# 5_way_switch_schematic.net
KiCad netlist of a schematic drawn in EAGLE
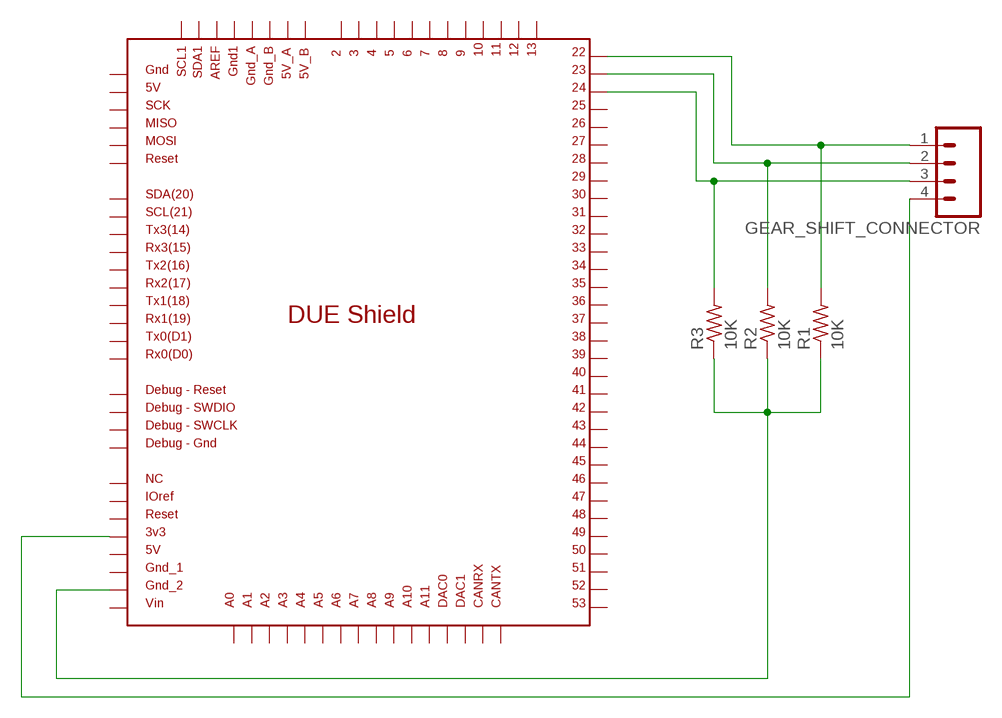
[diagram p0: schematic, sheet 1]

(export (version "E")
  (design (tool "Eeschema 10.0.6"))
  (components
    (comp (ref "GEAR_SHIFT_CONNECTOR")
      (value "M04JST-PTH-VERT")
      (footprint "eagle-import:JST-4-PTH-VERT")
      (libsource (lib "eagle-import") (part "M04JST-PTH-VERT"))
    )
    (comp (ref "R1")
      (value "10K")
      (footprint "eagle-import:0204_5")
      (libsource (lib "eagle-import") (part "R-US_0204/5"))
    )
    (comp (ref "R2")
      (value "10K")
      (footprint "eagle-import:0204_5")
      (libsource (lib "eagle-import") (part "R-US_0204/5"))
    )
    (comp (ref "R3")
      (value "10K")
      (footprint "eagle-import:0204_5")
      (libsource (lib "eagle-import") (part "R-US_0204/5"))
    )
    (comp (ref "U$1")
      (value "DUE(NORMAL)")
      (footprint "eagle-import:DUE(NORMAL)")
      (libsource (lib "eagle-import") (part "DUE(NORMAL)"))
    )
  )
  (nets
    (net (code "1") (name "Net-(GEAR_SHIFT_CONNECTOR-Pad1)") (class "Default")
      (node (ref "GEAR_SHIFT_CONNECTOR") (pin "1") (pinfunction "1_1") (pintype "passive"))
      (node (ref "R1") (pin "2") (pinfunction "2_2") (pintype "passive"))
      (node (ref "U$1") (pin "22") (pinfunction "22_22") (pintype "bidirectional"))
    )
    (net (code "2") (name "Net-(GEAR_SHIFT_CONNECTOR-Pad2)") (class "Default")
      (node (ref "GEAR_SHIFT_CONNECTOR") (pin "2") (pinfunction "2_2") (pintype "passive"))
      (node (ref "R2") (pin "2") (pinfunction "2_2") (pintype "passive"))
      (node (ref "U$1") (pin "23") (pinfunction "23_23") (pintype "bidirectional"))
    )
    (net (code "3") (name "Net-(GEAR_SHIFT_CONNECTOR-Pad3)") (class "Default")
      (node (ref "GEAR_SHIFT_CONNECTOR") (pin "3") (pinfunction "3_3") (pintype "passive"))
      (node (ref "R3") (pin "2") (pinfunction "2_2") (pintype "passive"))
      (node (ref "U$1") (pin "24") (pinfunction "24_24") (pintype "bidirectional"))
    )
    (net (code "4") (name "Net-(GEAR_SHIFT_CONNECTOR-Pad4)") (class "Default")
      (node (ref "GEAR_SHIFT_CONNECTOR") (pin "4") (pinfunction "4_4") (pintype "passive"))
      (node (ref "U$1") (pin "3V3") (pinfunction "3V3_3V3") (pintype "bidirectional"))
    )
    (net (code "5") (name "Net-(R1-Pad1)") (class "Default")
      (node (ref "R1") (pin "1") (pinfunction "1_1") (pintype "passive"))
      (node (ref "R2") (pin "1") (pinfunction "1_1") (pintype "passive"))
      (node (ref "R3") (pin "1") (pinfunction "1_1") (pintype "passive"))
      (node (ref "U$1") (pin "GND_2") (pinfunction "GND_2_GND_2") (pintype "bidirectional"))
    )
    (net (code "6") (name "unconnected-(U$1-Pad2)") (class "Default")
      (node (ref "U$1") (pin "2") (pinfunction "2_2") (pintype "bidirectional"))
    )
    (net (code "7") (name "unconnected-(U$1-Pad3)") (class "Default")
      (node (ref "U$1") (pin "3") (pinfunction "3_3") (pintype "bidirectional"))
    )
    (net (code "8") (name "unconnected-(U$1-Pad4)") (class "Default")
      (node (ref "U$1") (pin "4") (pinfunction "4_4") (pintype "bidirectional"))
    )
    (net (code "9") (name "unconnected-(U$1-Pad5)") (class "Default")
      (node (ref "U$1") (pin "5") (pinfunction "5_5") (pintype "bidirectional"))
    )
    (net (code "10") (name "unconnected-(U$1-Pad5V)") (class "Default")
      (node (ref "U$1") (pin "5V") (pinfunction "5V_5V") (pintype "bidirectional"))
    )
    (net (code "11") (name "unconnected-(U$1-Pad5V_A)") (class "Default")
      (node (ref "U$1") (pin "5V_A") (pinfunction "5V_A_5V_A") (pintype "bidirectional"))
    )
    (net (code "12") (name "unconnected-(U$1-Pad5V_B)") (class "Default")
      (node (ref "U$1") (pin "5V_B") (pinfunction "5V_B_5V_B") (pintype "bidirectional"))
    )
    (net (code "13") (name "unconnected-(U$1-Pad5V_ICSP)") (class "Default")
      (node (ref "U$1") (pin "5V_ICSP") (pinfunction "5V_ICSP_5V_ICSP") (pintype "bidirectional"))
    )
    (net (code "14") (name "unconnected-(U$1-Pad6)") (class "Default")
      (node (ref "U$1") (pin "6") (pinfunction "6_6") (pintype "bidirectional"))
    )
    (net (code "15") (name "unconnected-(U$1-Pad7)") (class "Default")
      (node (ref "U$1") (pin "7") (pinfunction "7_7") (pintype "bidirectional"))
    )
    (net (code "16") (name "unconnected-(U$1-Pad8)") (class "Default")
      (node (ref "U$1") (pin "8") (pinfunction "8_8") (pintype "bidirectional"))
    )
    (net (code "17") (name "unconnected-(U$1-Pad9)") (class "Default")
      (node (ref "U$1") (pin "9") (pinfunction "9_9") (pintype "bidirectional"))
    )
    (net (code "18") (name "unconnected-(U$1-Pad10)") (class "Default")
      (node (ref "U$1") (pin "10") (pinfunction "10_10") (pintype "bidirectional"))
    )
    (net (code "19") (name "unconnected-(U$1-Pad11)") (class "Default")
      (node (ref "U$1") (pin "11") (pinfunction "11_11") (pintype "bidirectional"))
    )
    (net (code "20") (name "unconnected-(U$1-Pad12)") (class "Default")
      (node (ref "U$1") (pin "12") (pinfunction "12_12") (pintype "bidirectional"))
    )
    (net (code "21") (name "unconnected-(U$1-Pad13)") (class "Default")
      (node (ref "U$1") (pin "13") (pinfunction "13_13") (pintype "bidirectional"))
    )
    (net (code "22") (name "unconnected-(U$1-Pad25)") (class "Default")
      (node (ref "U$1") (pin "25") (pinfunction "25_25") (pintype "bidirectional"))
    )
    (net (code "23") (name "unconnected-(U$1-Pad26)") (class "Default")
      (node (ref "U$1") (pin "26") (pinfunction "26_26") (pintype "bidirectional"))
    )
    (net (code "24") (name "unconnected-(U$1-Pad27)") (class "Default")
      (node (ref "U$1") (pin "27") (pinfunction "27_27") (pintype "bidirectional"))
    )
    (net (code "25") (name "unconnected-(U$1-Pad28)") (class "Default")
      (node (ref "U$1") (pin "28") (pinfunction "28_28") (pintype "bidirectional"))
    )
    (net (code "26") (name "unconnected-(U$1-Pad29)") (class "Default")
      (node (ref "U$1") (pin "29") (pinfunction "29_29") (pintype "bidirectional"))
    )
    (net (code "27") (name "unconnected-(U$1-Pad30)") (class "Default")
      (node (ref "U$1") (pin "30") (pinfunction "30_30") (pintype "bidirectional"))
    )
    (net (code "28") (name "unconnected-(U$1-Pad31)") (class "Default")
      (node (ref "U$1") (pin "31") (pinfunction "31_31") (pintype "bidirectional"))
    )
    (net (code "29") (name "unconnected-(U$1-Pad32)") (class "Default")
      (node (ref "U$1") (pin "32") (pinfunction "32_32") (pintype "bidirectional"))
    )
    (net (code "30") (name "unconnected-(U$1-Pad33)") (class "Default")
      (node (ref "U$1") (pin "33") (pinfunction "33_33") (pintype "bidirectional"))
    )
    (net (code "31") (name "unconnected-(U$1-Pad34)") (class "Default")
      (node (ref "U$1") (pin "34") (pinfunction "34_34") (pintype "bidirectional"))
    )
    (net (code "32") (name "unconnected-(U$1-Pad35)") (class "Default")
      (node (ref "U$1") (pin "35") (pinfunction "35_35") (pintype "bidirectional"))
    )
    (net (code "33") (name "unconnected-(U$1-Pad36)") (class "Default")
      (node (ref "U$1") (pin "36") (pinfunction "36_36") (pintype "bidirectional"))
    )
    (net (code "34") (name "unconnected-(U$1-Pad37)") (class "Default")
      (node (ref "U$1") (pin "37") (pinfunction "37_37") (pintype "bidirectional"))
    )
    (net (code "35") (name "unconnected-(U$1-Pad38)") (class "Default")
      (node (ref "U$1") (pin "38") (pinfunction "38_38") (pintype "bidirectional"))
    )
    (net (code "36") (name "unconnected-(U$1-Pad39)") (class "Default")
      (node (ref "U$1") (pin "39") (pinfunction "39_39") (pintype "bidirectional"))
    )
    (net (code "37") (name "unconnected-(U$1-Pad40)") (class "Default")
      (node (ref "U$1") (pin "40") (pinfunction "40_40") (pintype "bidirectional"))
    )
    (net (code "38") (name "unconnected-(U$1-Pad41)") (class "Default")
      (node (ref "U$1") (pin "41") (pinfunction "41_41") (pintype "bidirectional"))
    )
    (net (code "39") (name "unconnected-(U$1-Pad42)") (class "Default")
      (node (ref "U$1") (pin "42") (pinfunction "42_42") (pintype "bidirectional"))
    )
    (net (code "40") (name "unconnected-(U$1-Pad43)") (class "Default")
      (node (ref "U$1") (pin "43") (pinfunction "43_43") (pintype "bidirectional"))
    )
    (net (code "41") (name "unconnected-(U$1-Pad44)") (class "Default")
      (node (ref "U$1") (pin "44") (pinfunction "44_44") (pintype "bidirectional"))
    )
    (net (code "42") (name "unconnected-(U$1-Pad45)") (class "Default")
      (node (ref "U$1") (pin "45") (pinfunction "45_45") (pintype "bidirectional"))
    )
    (net (code "43") (name "unconnected-(U$1-Pad46)") (class "Default")
      (node (ref "U$1") (pin "46") (pinfunction "46_46") (pintype "bidirectional"))
    )
    (net (code "44") (name "unconnected-(U$1-Pad47)") (class "Default")
      (node (ref "U$1") (pin "47") (pinfunction "47_47") (pintype "bidirectional"))
    )
    (net (code "45") (name "unconnected-(U$1-Pad48)") (class "Default")
      (node (ref "U$1") (pin "48") (pinfunction "48_48") (pintype "bidirectional"))
    )
    (net (code "46") (name "unconnected-(U$1-Pad49)") (class "Default")
      (node (ref "U$1") (pin "49") (pinfunction "49_49") (pintype "bidirectional"))
    )
    (net (code "47") (name "unconnected-(U$1-Pad50)") (class "Default")
      (node (ref "U$1") (pin "50") (pinfunction "50_50") (pintype "bidirectional"))
    )
    (net (code "48") (name "unconnected-(U$1-Pad51)") (class "Default")
      (node (ref "U$1") (pin "51") (pinfunction "51_51") (pintype "bidirectional"))
    )
    (net (code "49") (name "unconnected-(U$1-Pad52)") (class "Default")
      (node (ref "U$1") (pin "52") (pinfunction "52_52") (pintype "bidirectional"))
    )
    (net (code "50") (name "unconnected-(U$1-Pad53)") (class "Default")
      (node (ref "U$1") (pin "53") (pinfunction "53_53") (pintype "bidirectional"))
    )
    (net (code "51") (name "unconnected-(U$1-PadA0)") (class "Default")
      (node (ref "U$1") (pin "A0") (pinfunction "A0_A0") (pintype "bidirectional"))
    )
    (net (code "52") (name "unconnected-(U$1-PadA1)") (class "Default")
      (node (ref "U$1") (pin "A1") (pinfunction "A1_A1") (pintype "bidirectional"))
    )
    (net (code "53") (name "unconnected-(U$1-PadA2)") (class "Default")
      (node (ref "U$1") (pin "A2") (pinfunction "A2_A2") (pintype "bidirectional"))
    )
    (net (code "54") (name "unconnected-(U$1-PadA3)") (class "Default")
      (node (ref "U$1") (pin "A3") (pinfunction "A3_A3") (pintype "bidirectional"))
    )
    (net (code "55") (name "unconnected-(U$1-PadA4)") (class "Default")
      (node (ref "U$1") (pin "A4") (pinfunction "A4_A4") (pintype "bidirectional"))
    )
    (net (code "56") (name "unconnected-(U$1-PadA5)") (class "Default")
      (node (ref "U$1") (pin "A5") (pinfunction "A5_A5") (pintype "bidirectional"))
    )
    (net (code "57") (name "unconnected-(U$1-PadA6)") (class "Default")
      (node (ref "U$1") (pin "A6") (pinfunction "A6_A6") (pintype "bidirectional"))
    )
    (net (code "58") (name "unconnected-(U$1-PadA7)") (class "Default")
      (node (ref "U$1") (pin "A7") (pinfunction "A7_A7") (pintype "bidirectional"))
    )
    (net (code "59") (name "unconnected-(U$1-PadA8)") (class "Default")
      (node (ref "U$1") (pin "A8") (pinfunction "A8_A8") (pintype "bidirectional"))
    )
    (net (code "60") (name "unconnected-(U$1-PadA9)") (class "Default")
      (node (ref "U$1") (pin "A9") (pinfunction "A9_A9") (pintype "bidirectional"))
    )
    (net (code "61") (name "unconnected-(U$1-PadA10)") (class "Default")
      (node (ref "U$1") (pin "A10") (pinfunction "A10_A10") (pintype "bidirectional"))
    )
    (net (code "62") (name "unconnected-(U$1-PadA11)") (class "Default")
      (node (ref "U$1") (pin "A11") (pinfunction "A11_A11") (pintype "bidirectional"))
    )
    (net (code "63") (name "unconnected-(U$1-PadAREF)") (class "Default")
      (node (ref "U$1") (pin "AREF") (pinfunction "AREF_AREF") (pintype "bidirectional"))
    )
    (net (code "64") (name "unconnected-(U$1-PadCANRX)") (class "Default")
      (node (ref "U$1") (pin "CANRX") (pinfunction "CANRX_CANRX") (pintype "bidirectional"))
    )
    (net (code "65") (name "unconnected-(U$1-PadCANTX)") (class "Default")
      (node (ref "U$1") (pin "CANTX") (pinfunction "CANTX_CANTX") (pintype "bidirectional"))
    )
    (net (code "66") (name "unconnected-(U$1-PadDAC0)") (class "Default")
      (node (ref "U$1") (pin "DAC0") (pinfunction "DAC0_DAC0") (pintype "bidirectional"))
    )
    (net (code "67") (name "unconnected-(U$1-PadDAC1)") (class "Default")
      (node (ref "U$1") (pin "DAC1") (pinfunction "DAC1_DAC1") (pintype "bidirectional"))
    )
    (net (code "68") (name "unconnected-(U$1-PadGND1)") (class "Default")
      (node (ref "U$1") (pin "GND1") (pinfunction "GND1_GND1") (pintype "bidirectional"))
    )
    (net (code "69") (name "unconnected-(U$1-PadGND_1)") (class "Default")
      (node (ref "U$1") (pin "GND_1") (pinfunction "GND_1_GND_1") (pintype "bidirectional"))
    )
    (net (code "70") (name "unconnected-(U$1-PadGND_A)") (class "Default")
      (node (ref "U$1") (pin "GND_A") (pinfunction "GND_A_GND_A") (pintype "bidirectional"))
    )
    (net (code "71") (name "unconnected-(U$1-PadGND_B)") (class "Default")
      (node (ref "U$1") (pin "GND_B") (pinfunction "GND_B_GND_B") (pintype "bidirectional"))
    )
    (net (code "72") (name "unconnected-(U$1-PadGND_DEBUG)") (class "Default")
      (node (ref "U$1") (pin "GND_DEBUG") (pinfunction "GND_DEBUG_GND_DEBUG") (pintype "bidirectional"))
    )
    (net (code "73") (name "unconnected-(U$1-PadGND_ICSP)") (class "Default")
      (node (ref "U$1") (pin "GND_ICSP") (pinfunction "GND_ICSP_GND_ICSP") (pintype "bidirectional"))
    )
    (net (code "74") (name "unconnected-(U$1-PadIOREF)") (class "Default")
      (node (ref "U$1") (pin "IOREF") (pinfunction "IOREF_IOREF") (pintype "bidirectional"))
    )
    (net (code "75") (name "unconnected-(U$1-PadMISO_ICSP)") (class "Default")
      (node (ref "U$1") (pin "MISO_ICSP") (pinfunction "MISO_ICSP_MISO_ICSP") (pintype "bidirectional"))
    )
    (net (code "76") (name "unconnected-(U$1-PadMOSI_ICSP)") (class "Default")
      (node (ref "U$1") (pin "MOSI_ICSP") (pinfunction "MOSI_ICSP_MOSI_ICSP") (pintype "bidirectional"))
    )
    (net (code "77") (name "unconnected-(U$1-PadNC)") (class "Default")
      (node (ref "U$1") (pin "NC") (pinfunction "NC_NC") (pintype "bidirectional"))
    )
    (net (code "78") (name "unconnected-(U$1-PadRESET)") (class "Default")
      (node (ref "U$1") (pin "RESET") (pinfunction "RESET_RESET") (pintype "bidirectional"))
    )
    (net (code "79") (name "unconnected-(U$1-PadRESET_DEBUG)") (class "Default")
      (node (ref "U$1") (pin "RESET_DEBUG") (pinfunction "RESET_DEBUG_RESET_DEBUG") (pintype "bidirectional"))
    )
    (net (code "80") (name "unconnected-(U$1-PadRESET_ICSP)") (class "Default")
      (node (ref "U$1") (pin "RESET_ICSP") (pinfunction "RESET_ICSP_RESET_ICSP") (pintype "bidirectional"))
    )
    (net (code "81") (name "unconnected-(U$1-PadRX0)") (class "Default")
      (node (ref "U$1") (pin "RX0") (pinfunction "RX0_RX0") (pintype "bidirectional"))
    )
    (net (code "82") (name "unconnected-(U$1-PadRX1)") (class "Default")
      (node (ref "U$1") (pin "RX1") (pinfunction "RX1_RX1") (pintype "bidirectional"))
    )
    (net (code "83") (name "unconnected-(U$1-PadRX2)") (class "Default")
      (node (ref "U$1") (pin "RX2") (pinfunction "RX2_RX2") (pintype "bidirectional"))
    )
    (net (code "84") (name "unconnected-(U$1-PadRX3)") (class "Default")
      (node (ref "U$1") (pin "RX3") (pinfunction "RX3_RX3") (pintype "bidirectional"))
    )
    (net (code "85") (name "unconnected-(U$1-PadSCK_ICSP)") (class "Default")
      (node (ref "U$1") (pin "SCK_ICSP") (pinfunction "SCK_ICSP_SCK_ICSP") (pintype "bidirectional"))
    )
    (net (code "86") (name "unconnected-(U$1-PadSCL)") (class "Default")
      (node (ref "U$1") (pin "SCL") (pinfunction "SCL_SCL") (pintype "bidirectional"))
    )
    (net (code "87") (name "unconnected-(U$1-PadSCL1)") (class "Default")
      (node (ref "U$1") (pin "SCL1") (pinfunction "SCL1_SCL1") (pintype "bidirectional"))
    )
    (net (code "88") (name "unconnected-(U$1-PadSDA)") (class "Default")
      (node (ref "U$1") (pin "SDA") (pinfunction "SDA_SDA") (pintype "bidirectional"))
    )
    (net (code "89") (name "unconnected-(U$1-PadSDA1)") (class "Default")
      (node (ref "U$1") (pin "SDA1") (pinfunction "SDA1_SDA1") (pintype "bidirectional"))
    )
    (net (code "90") (name "unconnected-(U$1-PadSWCLK_DEBUG)") (class "Default")
      (node (ref "U$1") (pin "SWCLK_DEBUG") (pinfunction "SWCLK_DEBUG_SWCLK_DEBUG") (pintype "bidirectional"))
    )
    (net (code "91") (name "unconnected-(U$1-PadSWDIO_DEBUG)") (class "Default")
      (node (ref "U$1") (pin "SWDIO_DEBUG") (pinfunction "SWDIO_DEBUG_SWDIO_DEBUG") (pintype "bidirectional"))
    )
    (net (code "92") (name "unconnected-(U$1-PadTX0)") (class "Default")
      (node (ref "U$1") (pin "TX0") (pinfunction "TX0_TX0") (pintype "bidirectional"))
    )
    (net (code "93") (name "unconnected-(U$1-PadTX1)") (class "Default")
      (node (ref "U$1") (pin "TX1") (pinfunction "TX1_TX1") (pintype "bidirectional"))
    )
    (net (code "94") (name "unconnected-(U$1-PadTX2)") (class "Default")
      (node (ref "U$1") (pin "TX2") (pinfunction "TX2_TX2") (pintype "bidirectional"))
    )
    (net (code "95") (name "unconnected-(U$1-PadTX3)") (class "Default")
      (node (ref "U$1") (pin "TX3") (pinfunction "TX3_TX3") (pintype "bidirectional"))
    )
    (net (code "96") (name "unconnected-(U$1-PadVIN)") (class "Default")
      (node (ref "U$1") (pin "VIN") (pinfunction "VIN_VIN") (pintype "bidirectional"))
    )
  )
)
